# T61_LC_Scanner.net
KiCad netlist of a schematic drawn in EAGLE
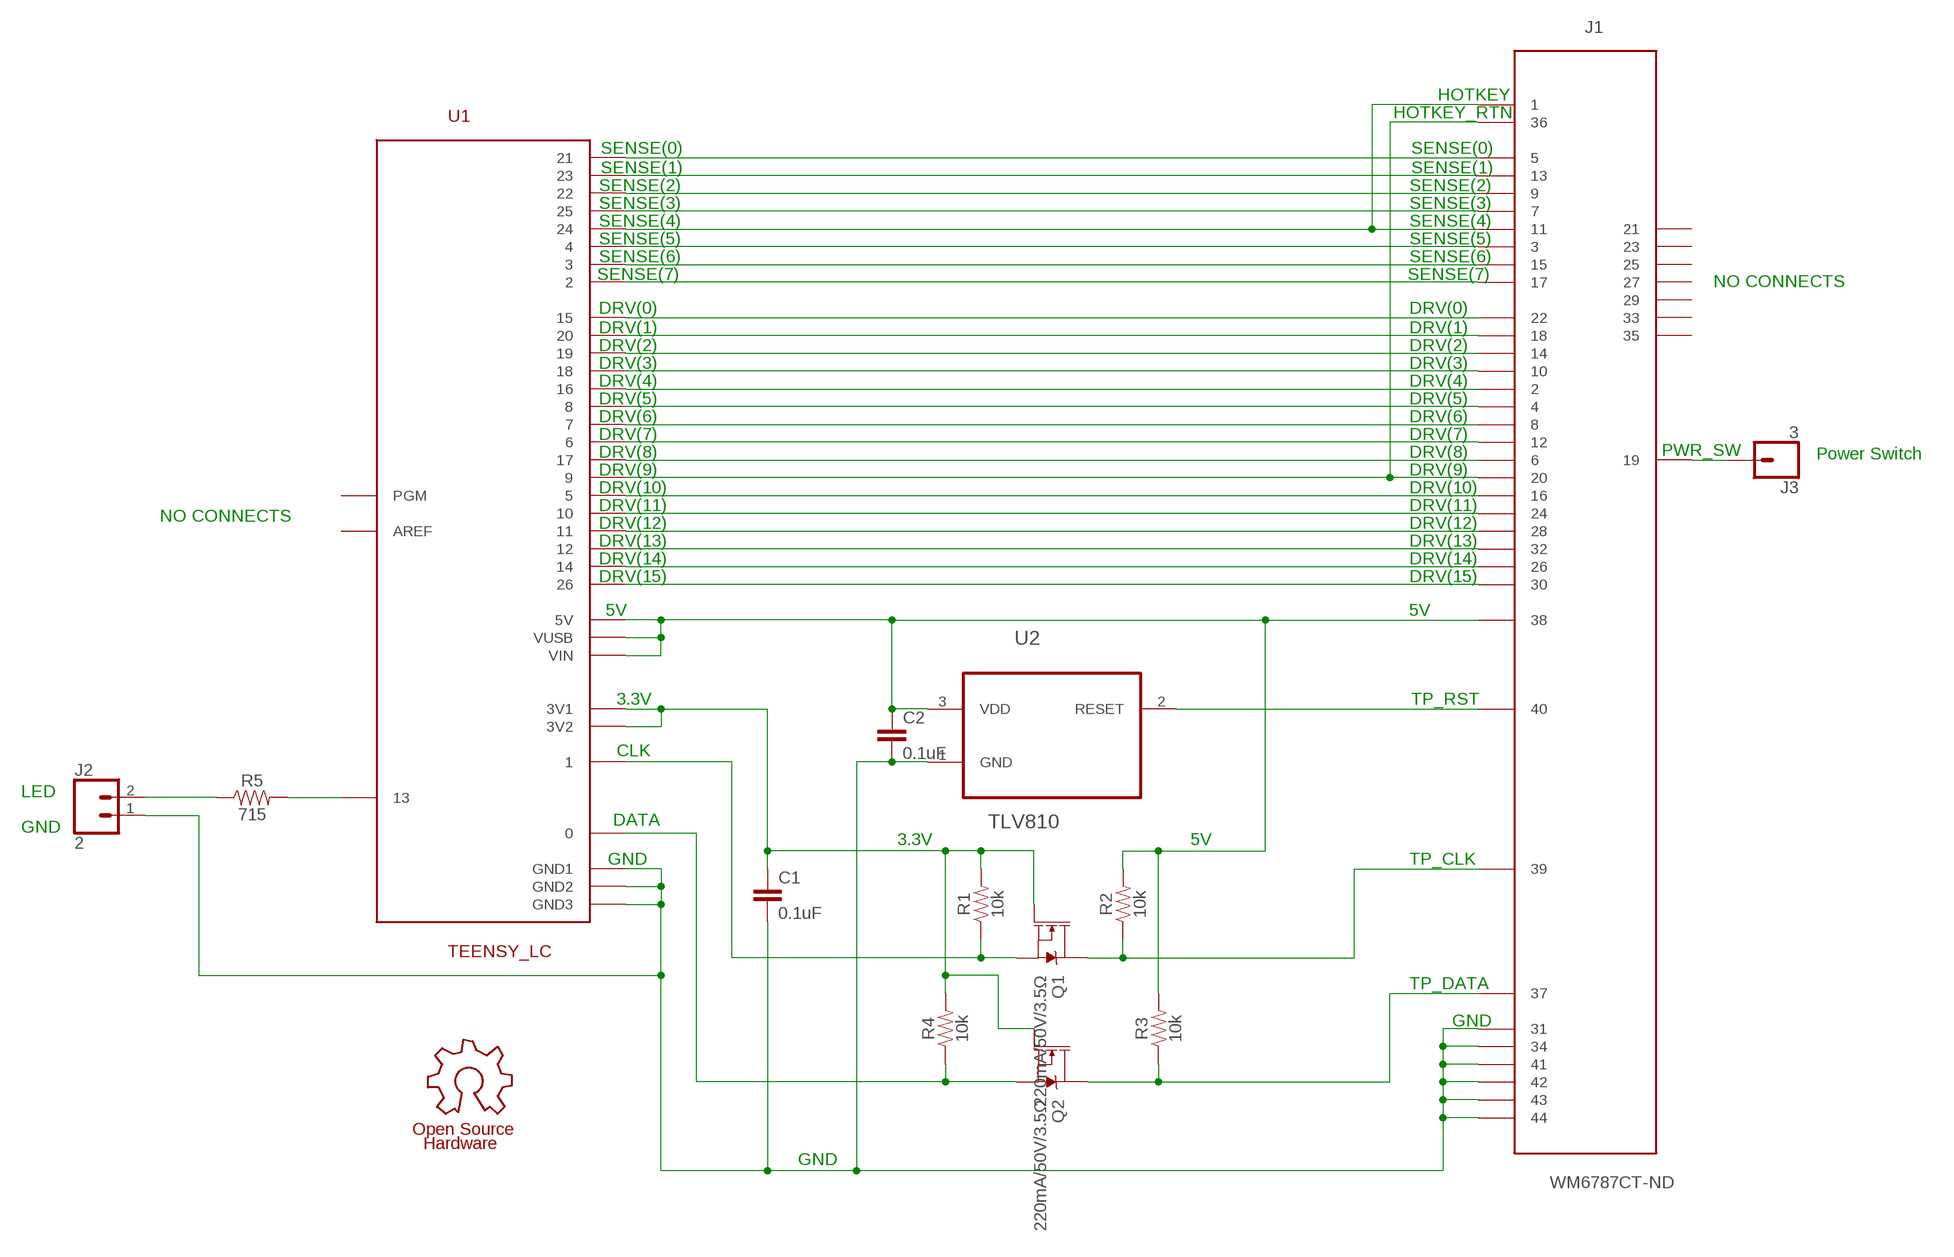
[diagram p0: schematic, sheet 1]

(export (version "E")
  (design (tool "Eeschema 10.0.6"))
  (components
    (comp (ref "C1")
      (value "0.1uF")
      (footprint "eagle-import:0603")
      (libsource (lib "eagle-import") (part "0.1UF-0603-25V-(+80/-20%)"))
    )
    (comp (ref "C2")
      (value "0.1uF")
      (footprint "eagle-import:0603")
      (libsource (lib "eagle-import") (part "0.1UF-0603-25V-(+80/-20%)"))
    )
    (comp (ref "GOLD_ORB_SM1")
      (value "OSHWLOGOLOGO5MM")
      (footprint "eagle-import:OSHW_5MM")
      (libsource (lib "eagle-import") (part "OSHWLOGOLOGO5MM"))
    )
    (comp (ref "J1")
      (value "WM6787CT-ND")
      (footprint "eagle-import:WM6787CT-ND")
      (libsource (lib "eagle-import") (part "WM6787CT-ND"))
    )
    (comp (ref "J2")
      (value "2")
      (footprint "eagle-import:1X02")
      (libsource (lib "eagle-import") (part "CONN_02"))
    )
    (comp (ref "J3")
      (value "3")
      (footprint "eagle-import:1X01")
      (libsource (lib "eagle-import") (part "CONN_01"))
    )
    (comp (ref "Q1")
      (value "220mA/50V/3.5Ω")
      (footprint "eagle-import:SOT23-3")
      (libsource (lib "eagle-import") (part "MOSFET-NCH-BSS138"))
    )
    (comp (ref "Q2")
      (value "220mA/50V/3.5Ω")
      (footprint "eagle-import:SOT23-3")
      (libsource (lib "eagle-import") (part "MOSFET-NCH-BSS138"))
    )
    (comp (ref "R1")
      (value "10k")
      (footprint "eagle-import:0603")
      (libsource (lib "eagle-import") (part "10KOHM-0603-1/10W-1%"))
    )
    (comp (ref "R2")
      (value "10k")
      (footprint "eagle-import:0603")
      (libsource (lib "eagle-import") (part "10KOHM-0603-1/10W-1%"))
    )
    (comp (ref "R3")
      (value "10k")
      (footprint "eagle-import:0603")
      (libsource (lib "eagle-import") (part "10KOHM-0603-1/10W-1%"))
    )
    (comp (ref "R4")
      (value "10k")
      (footprint "eagle-import:0603")
      (libsource (lib "eagle-import") (part "10KOHM-0603-1/10W-1%"))
    )
    (comp (ref "R5")
      (value "715")
      (footprint "eagle-import:0603")
      (libsource (lib "eagle-import") (part "715OHM-0603-1/10W-1%"))
    )
    (comp (ref "U1")
      (value "TEENSY_LC")
      (footprint "eagle-import:TEENSY_LC")
      (libsource (lib "eagle-import") (part "TEENSY_LC"))
    )
    (comp (ref "U2")
      (value "TLV810SDBZT")
      (footprint "eagle-import:SOT95P237X112-3N")
      (fields (field (name "MF") "Texas Instruments"))
      (libsource (lib "eagle-import") (part "TLV810SDBZT"))
    )
  )
  (nets
    (net (code "1") (name "Net-(J1-1)") (class "Default")
      (node (ref "J1") (pin "P$1") (pinfunction "1_P$1") (pintype "bidirectional"))
      (node (ref "J1") (pin "P$11") (pinfunction "11_P$11") (pintype "bidirectional"))
      (node (ref "U1") (pin "24") (pinfunction "24_24") (pintype "bidirectional"))
    )
    (net (code "2") (name "Net-(J1-2)") (class "Default")
      (node (ref "J1") (pin "P$2") (pinfunction "2_P$2") (pintype "bidirectional"))
      (node (ref "U1") (pin "16") (pinfunction "16_16") (pintype "bidirectional"))
    )
    (net (code "3") (name "Net-(J1-3)") (class "Default")
      (node (ref "J1") (pin "P$3") (pinfunction "3_P$3") (pintype "bidirectional"))
      (node (ref "U1") (pin "4") (pinfunction "4_4") (pintype "bidirectional"))
    )
    (net (code "4") (name "Net-(J1-4)") (class "Default")
      (node (ref "J1") (pin "P$4") (pinfunction "4_P$4") (pintype "bidirectional"))
      (node (ref "U1") (pin "8") (pinfunction "8_8") (pintype "bidirectional"))
    )
    (net (code "5") (name "Net-(J1-5)") (class "Default")
      (node (ref "J1") (pin "P$5") (pinfunction "5_P$5") (pintype "bidirectional"))
      (node (ref "U1") (pin "21") (pinfunction "21_21") (pintype "bidirectional"))
    )
    (net (code "6") (name "Net-(J1-6)") (class "Default")
      (node (ref "J1") (pin "P$6") (pinfunction "6_P$6") (pintype "bidirectional"))
      (node (ref "U1") (pin "17") (pinfunction "17_17") (pintype "bidirectional"))
    )
    (net (code "7") (name "Net-(J1-7)") (class "Default")
      (node (ref "J1") (pin "P$7") (pinfunction "7_P$7") (pintype "bidirectional"))
      (node (ref "U1") (pin "25") (pinfunction "25_25") (pintype "bidirectional"))
    )
    (net (code "8") (name "Net-(J1-8)") (class "Default")
      (node (ref "J1") (pin "P$8") (pinfunction "8_P$8") (pintype "bidirectional"))
      (node (ref "U1") (pin "7") (pinfunction "7_7") (pintype "bidirectional"))
    )
    (net (code "9") (name "Net-(J1-9)") (class "Default")
      (node (ref "J1") (pin "P$9") (pinfunction "9_P$9") (pintype "bidirectional"))
      (node (ref "U1") (pin "22") (pinfunction "22_22") (pintype "bidirectional"))
    )
    (net (code "10") (name "Net-(J1-10)") (class "Default")
      (node (ref "J1") (pin "P$10") (pinfunction "10_P$10") (pintype "bidirectional"))
      (node (ref "U1") (pin "18") (pinfunction "18_18") (pintype "bidirectional"))
    )
    (net (code "11") (name "Net-(J1-12)") (class "Default")
      (node (ref "J1") (pin "P$12") (pinfunction "12_P$12") (pintype "bidirectional"))
      (node (ref "U1") (pin "6") (pinfunction "6_6") (pintype "bidirectional"))
    )
    (net (code "12") (name "Net-(J1-13)") (class "Default")
      (node (ref "J1") (pin "P$13") (pinfunction "13_P$13") (pintype "bidirectional"))
      (node (ref "U1") (pin "23") (pinfunction "23_23") (pintype "bidirectional"))
    )
    (net (code "13") (name "Net-(J1-14)") (class "Default")
      (node (ref "J1") (pin "P$14") (pinfunction "14_P$14") (pintype "bidirectional"))
      (node (ref "U1") (pin "19") (pinfunction "19_19") (pintype "bidirectional"))
    )
    (net (code "14") (name "Net-(J1-15)") (class "Default")
      (node (ref "J1") (pin "P$15") (pinfunction "15_P$15") (pintype "bidirectional"))
      (node (ref "U1") (pin "3") (pinfunction "3_3") (pintype "bidirectional"))
    )
    (net (code "15") (name "Net-(J1-16)") (class "Default")
      (node (ref "J1") (pin "P$16") (pinfunction "16_P$16") (pintype "bidirectional"))
      (node (ref "U1") (pin "5") (pinfunction "5_5") (pintype "bidirectional"))
    )
    (net (code "16") (name "Net-(J1-17)") (class "Default")
      (node (ref "J1") (pin "P$17") (pinfunction "17_P$17") (pintype "bidirectional"))
      (node (ref "U1") (pin "2") (pinfunction "2_2") (pintype "bidirectional"))
    )
    (net (code "17") (name "Net-(J1-18)") (class "Default")
      (node (ref "J1") (pin "P$18") (pinfunction "18_P$18") (pintype "bidirectional"))
      (node (ref "U1") (pin "20") (pinfunction "20_20") (pintype "bidirectional"))
    )
    (net (code "18") (name "Net-(J1-19)") (class "Default")
      (node (ref "J1") (pin "P$19") (pinfunction "19_P$19") (pintype "bidirectional"))
      (node (ref "J3") (pin "1") (pinfunction "1_1") (pintype "passive"))
    )
    (net (code "19") (name "Net-(J1-20)") (class "Default")
      (node (ref "J1") (pin "P$20") (pinfunction "20_P$20") (pintype "bidirectional"))
      (node (ref "J1") (pin "P$36") (pinfunction "36_P$36") (pintype "bidirectional"))
      (node (ref "U1") (pin "9") (pinfunction "9_9") (pintype "bidirectional"))
    )
    (net (code "20") (name "Net-(J1-22)") (class "Default")
      (node (ref "J1") (pin "P$22") (pinfunction "22_P$22") (pintype "bidirectional"))
      (node (ref "U1") (pin "15") (pinfunction "15_15") (pintype "bidirectional"))
    )
    (net (code "21") (name "Net-(J1-24)") (class "Default")
      (node (ref "J1") (pin "P$24") (pinfunction "24_P$24") (pintype "bidirectional"))
      (node (ref "U1") (pin "10") (pinfunction "10_10") (pintype "bidirectional"))
    )
    (net (code "22") (name "Net-(J1-26)") (class "Default")
      (node (ref "J1") (pin "P$26") (pinfunction "26_P$26") (pintype "bidirectional"))
      (node (ref "U1") (pin "14") (pinfunction "14_14") (pintype "bidirectional"))
    )
    (net (code "23") (name "Net-(J1-28)") (class "Default")
      (node (ref "J1") (pin "P$28") (pinfunction "28_P$28") (pintype "bidirectional"))
      (node (ref "U1") (pin "11") (pinfunction "11_11") (pintype "bidirectional"))
    )
    (net (code "24") (name "Net-(J1-30)") (class "Default")
      (node (ref "J1") (pin "P$30") (pinfunction "30_P$30") (pintype "bidirectional"))
      (node (ref "U1") (pin "26") (pinfunction "26_26") (pintype "bidirectional"))
    )
    (net (code "25") (name "Net-(J1-31)") (class "Default")
      (node (ref "C1") (pin "2") (pinfunction "2_2") (pintype "passive"))
      (node (ref "C2") (pin "2") (pinfunction "2_2") (pintype "passive"))
      (node (ref "J1") (pin "P$31") (pinfunction "31_P$31") (pintype "bidirectional"))
      (node (ref "J1") (pin "P$34") (pinfunction "34_P$34") (pintype "bidirectional"))
      (node (ref "J1") (pin "P$41") (pinfunction "43_P$41") (pintype "bidirectional"))
      (node (ref "J1") (pin "P$42") (pinfunction "44_P$42") (pintype "bidirectional"))
      (node (ref "J1") (pin "P$43") (pinfunction "41_P$43") (pintype "bidirectional"))
      (node (ref "J1") (pin "P$44") (pinfunction "42_P$44") (pintype "bidirectional"))
      (node (ref "J2") (pin "1") (pinfunction "1_1") (pintype "passive"))
      (node (ref "U1") (pin "GND1") (pinfunction "GND1_GND1") (pintype "bidirectional"))
      (node (ref "U1") (pin "GND2") (pinfunction "GND2_GND2") (pintype "bidirectional"))
      (node (ref "U1") (pin "GND3") (pinfunction "GND3_GND3") (pintype "bidirectional"))
      (node (ref "U2") (pin "1") (pinfunction "GND_1") (pintype "passive"))
    )
    (net (code "26") (name "Net-(J1-32)") (class "Default")
      (node (ref "J1") (pin "P$32") (pinfunction "32_P$32") (pintype "bidirectional"))
      (node (ref "U1") (pin "12") (pinfunction "12_12") (pintype "bidirectional"))
    )
    (net (code "27") (name "Net-(J1-37)") (class "Default")
      (node (ref "J1") (pin "P$37") (pinfunction "37_P$37") (pintype "bidirectional"))
      (node (ref "Q2") (pin "3") (pinfunction "D_3") (pintype "bidirectional"))
      (node (ref "R3") (pin "1") (pinfunction "1_1") (pintype "passive"))
    )
    (net (code "28") (name "Net-(J1-38)") (class "Default")
      (node (ref "C2") (pin "1") (pinfunction "1_1") (pintype "passive"))
      (node (ref "J1") (pin "P$38") (pinfunction "38_P$38") (pintype "bidirectional"))
      (node (ref "R2") (pin "2") (pinfunction "2_2") (pintype "passive"))
      (node (ref "R3") (pin "2") (pinfunction "2_2") (pintype "passive"))
      (node (ref "U1") (pin "5V") (pinfunction "5V_5V") (pintype "bidirectional"))
      (node (ref "U1") (pin "VIN") (pinfunction "VIN_VIN") (pintype "bidirectional"))
      (node (ref "U1") (pin "VUSB") (pinfunction "VUSB_VUSB") (pintype "bidirectional"))
      (node (ref "U2") (pin "3") (pinfunction "VDD_3") (pintype "power_in"))
    )
    (net (code "29") (name "Net-(J1-39)") (class "Default")
      (node (ref "J1") (pin "P$39") (pinfunction "39_P$39") (pintype "bidirectional"))
      (node (ref "Q1") (pin "3") (pinfunction "D_3") (pintype "bidirectional"))
      (node (ref "R2") (pin "1") (pinfunction "1_1") (pintype "passive"))
    )
    (net (code "30") (name "Net-(J1-40)") (class "Default")
      (node (ref "J1") (pin "P$40") (pinfunction "40_P$40") (pintype "bidirectional"))
      (node (ref "U2") (pin "2") (pinfunction "RESET_2") (pintype "output"))
    )
    (net (code "31") (name "Net-(J2-Pad2)") (class "Default")
      (node (ref "J2") (pin "2") (pinfunction "2_2") (pintype "passive"))
      (node (ref "R5") (pin "1") (pinfunction "1_1") (pintype "passive"))
    )
    (net (code "32") (name "Net-(Q1-G)") (class "Default")
      (node (ref "C1") (pin "1") (pinfunction "1_1") (pintype "passive"))
      (node (ref "Q1") (pin "1") (pinfunction "G_1") (pintype "bidirectional"))
      (node (ref "Q2") (pin "1") (pinfunction "G_1") (pintype "bidirectional"))
      (node (ref "R1") (pin "2") (pinfunction "2_2") (pintype "passive"))
      (node (ref "R4") (pin "2") (pinfunction "2_2") (pintype "passive"))
      (node (ref "U1") (pin "3V1") (pinfunction "3V1_3V1") (pintype "bidirectional"))
      (node (ref "U1") (pin "3V2") (pinfunction "3V2_3V2") (pintype "bidirectional"))
    )
    (net (code "33") (name "Net-(Q1-S)") (class "Default")
      (node (ref "Q1") (pin "2") (pinfunction "S_2") (pintype "bidirectional"))
      (node (ref "R1") (pin "1") (pinfunction "1_1") (pintype "passive"))
      (node (ref "U1") (pin "1") (pinfunction "1_1") (pintype "bidirectional"))
    )
    (net (code "34") (name "Net-(Q2-S)") (class "Default")
      (node (ref "Q2") (pin "2") (pinfunction "S_2") (pintype "bidirectional"))
      (node (ref "R4") (pin "1") (pinfunction "1_1") (pintype "passive"))
      (node (ref "U1") (pin "0") (pinfunction "0_0") (pintype "bidirectional"))
    )
    (net (code "35") (name "Net-(R5-Pad2)") (class "Default")
      (node (ref "R5") (pin "2") (pinfunction "2_2") (pintype "passive"))
      (node (ref "U1") (pin "13") (pinfunction "13_13") (pintype "bidirectional"))
    )
    (net (code "36") (name "unconnected-(J1-21-PadP$21)") (class "Default")
      (node (ref "J1") (pin "P$21") (pinfunction "21_P$21") (pintype "bidirectional"))
    )
    (net (code "37") (name "unconnected-(J1-23-PadP$23)") (class "Default")
      (node (ref "J1") (pin "P$23") (pinfunction "23_P$23") (pintype "bidirectional"))
    )
    (net (code "38") (name "unconnected-(J1-25-PadP$25)") (class "Default")
      (node (ref "J1") (pin "P$25") (pinfunction "25_P$25") (pintype "bidirectional"))
    )
    (net (code "39") (name "unconnected-(J1-27-PadP$27)") (class "Default")
      (node (ref "J1") (pin "P$27") (pinfunction "27_P$27") (pintype "bidirectional"))
    )
    (net (code "40") (name "unconnected-(J1-29-PadP$29)") (class "Default")
      (node (ref "J1") (pin "P$29") (pinfunction "29_P$29") (pintype "bidirectional"))
    )
    (net (code "41") (name "unconnected-(J1-33-PadP$33)") (class "Default")
      (node (ref "J1") (pin "P$33") (pinfunction "33_P$33") (pintype "bidirectional"))
    )
    (net (code "42") (name "unconnected-(J1-35-PadP$35)") (class "Default")
      (node (ref "J1") (pin "P$35") (pinfunction "35_P$35") (pintype "bidirectional"))
    )
    (net (code "43") (name "unconnected-(U1-PadAREF)") (class "Default")
      (node (ref "U1") (pin "AREF") (pinfunction "AREF_AREF") (pintype "bidirectional"))
    )
    (net (code "44") (name "unconnected-(U1-PadPGM)") (class "Default")
      (node (ref "U1") (pin "PGM") (pinfunction "PGM_PGM") (pintype "bidirectional"))
    )
  )
)
